# breakout.net
KiCad netlist of a schematic drawn in EAGLE
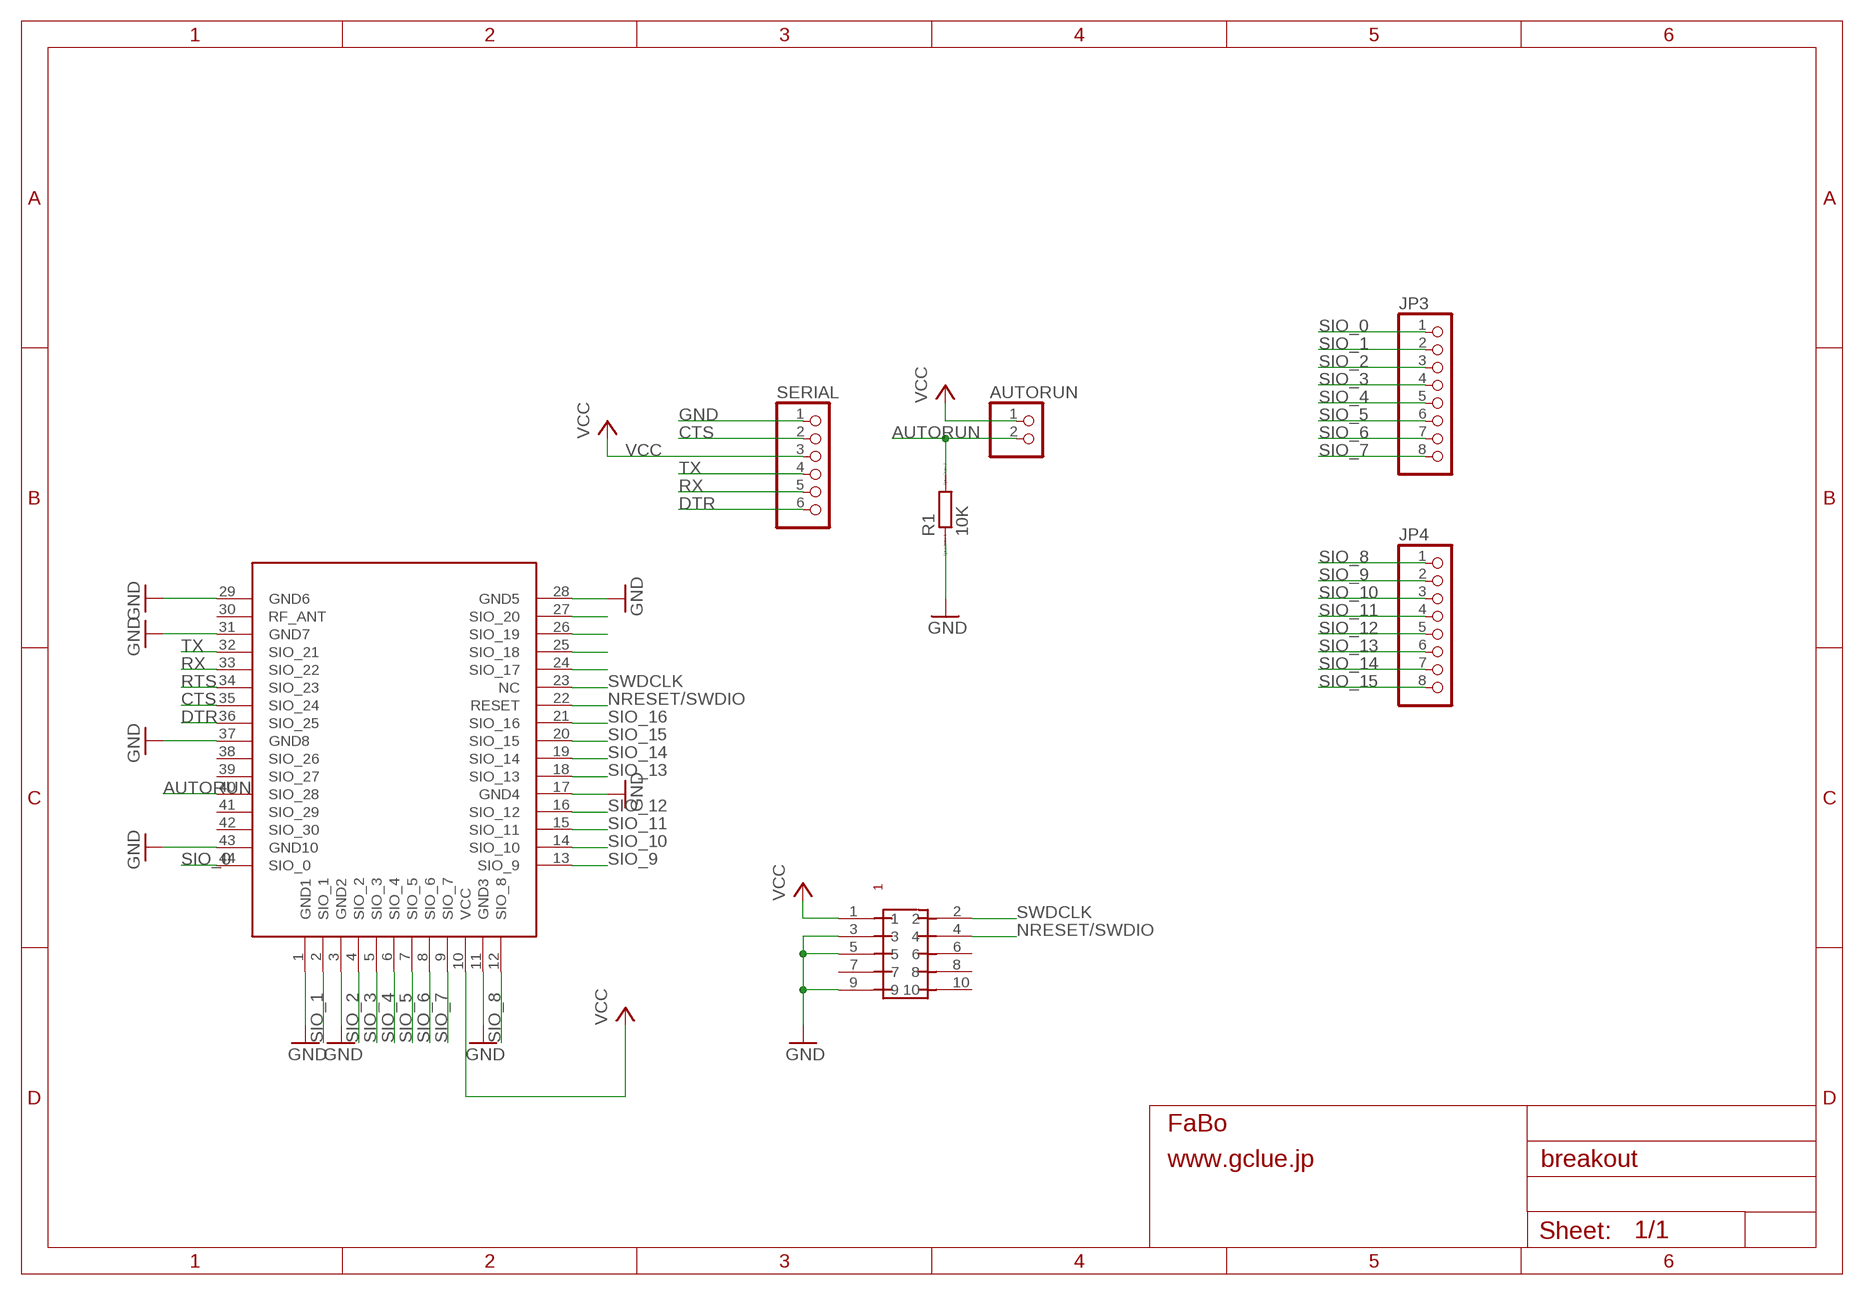
[diagram p0: schematic, sheet 1]

(export (version "E")
  (design (tool "Eeschema 10.0.6"))
  (components
    (comp (ref "AUTORUN")
      (value "PINHD-1X2")
      (footprint "eagle-import:1X02")
      (libsource (lib "eagle-import") (part "PINHD-1X2"))
    )
    (comp (ref "BL1")
      (value "LAIRD-BL600")
      (footprint "eagle-import:LAIRD-BL600")
      (libsource (lib "eagle-import") (part "LAIRD-BL600"))
    )
    (comp (ref "JP3")
      (value "PINHD-1X8-3.5MM")
      (footprint "eagle-import:1X08-3.5MM")
      (libsource (lib "eagle-import") (part "PINHD-1X8-3.5MM"))
    )
    (comp (ref "JP4")
      (value "PINHD-1X8-3.5MM")
      (footprint "eagle-import:1X08-3.5MM")
      (libsource (lib "eagle-import") (part "PINHD-1X8-3.5MM"))
    )
    (comp (ref "R1")
      (value "10K")
      (footprint "eagle-import:R0603")
      (libsource (lib "eagle-import") (part "RR0603"))
    )
    (comp (ref "SERIAL")
      (value "PINHD-1X6")
      (footprint "eagle-import:1X06")
      (libsource (lib "eagle-import") (part "PINHD-1X6"))
    )
    (comp (ref "U$1")
      (value "PIN-HEADER-SMT(1.27MM)2X5")
      (footprint "eagle-import:PIN-HEADER-SMT(1.27MM)2X5")
      (libsource (lib "eagle-import") (part "PIN-HEADER-SMT(1.27MM)2X5"))
    )
  )
  (nets
    (net (code "1") (name "/AUTORUN") (class "Default")
      (node (ref "AUTORUN") (pin "2") (pinfunction "2_2") (pintype "passive"))
      (node (ref "BL1") (pin "40") (pinfunction "SIO_28_40") (pintype "bidirectional"))
      (node (ref "R1") (pin "2") (pinfunction "2_2") (pintype "passive"))
    )
    (net (code "2") (name "/CTS") (class "Default")
      (node (ref "BL1") (pin "35") (pinfunction "SIO_24_35") (pintype "bidirectional"))
      (node (ref "SERIAL") (pin "2") (pinfunction "2_2") (pintype "passive"))
    )
    (net (code "3") (name "/DTR") (class "Default")
      (node (ref "BL1") (pin "36") (pinfunction "SIO_25_36") (pintype "bidirectional"))
      (node (ref "SERIAL") (pin "6") (pinfunction "6_6") (pintype "passive"))
    )
    (net (code "4") (name "/NRESET{slash}SWDIO") (class "Default")
      (node (ref "BL1") (pin "22") (pinfunction "RESET_22") (pintype "bidirectional"))
      (node (ref "U$1") (pin "4") (pinfunction "4_4") (pintype "bidirectional"))
    )
    (net (code "5") (name "/RTS") (class "Default")
      (node (ref "BL1") (pin "34") (pinfunction "SIO_23_34") (pintype "bidirectional"))
    )
    (net (code "6") (name "/RX") (class "Default")
      (node (ref "BL1") (pin "33") (pinfunction "SIO_22_33") (pintype "bidirectional"))
      (node (ref "SERIAL") (pin "5") (pinfunction "5_5") (pintype "passive"))
    )
    (net (code "7") (name "/SIO_0") (class "Default")
      (node (ref "BL1") (pin "44") (pinfunction "SIO_0_44") (pintype "bidirectional"))
      (node (ref "JP3") (pin "1") (pinfunction "1_1") (pintype "passive"))
    )
    (net (code "8") (name "/SIO_1") (class "Default")
      (node (ref "BL1") (pin "2") (pinfunction "SIO_1_2") (pintype "bidirectional"))
      (node (ref "JP3") (pin "2") (pinfunction "2_2") (pintype "passive"))
    )
    (net (code "9") (name "/SIO_2") (class "Default")
      (node (ref "BL1") (pin "4") (pinfunction "SIO_2_4") (pintype "bidirectional"))
      (node (ref "JP3") (pin "3") (pinfunction "3_3") (pintype "passive"))
    )
    (net (code "10") (name "/SIO_3") (class "Default")
      (node (ref "BL1") (pin "5") (pinfunction "SIO_3_5") (pintype "bidirectional"))
      (node (ref "JP3") (pin "4") (pinfunction "4_4") (pintype "passive"))
    )
    (net (code "11") (name "/SIO_4") (class "Default")
      (node (ref "BL1") (pin "6") (pinfunction "SIO_4_6") (pintype "bidirectional"))
      (node (ref "JP3") (pin "5") (pinfunction "5_5") (pintype "passive"))
    )
    (net (code "12") (name "/SIO_5") (class "Default")
      (node (ref "BL1") (pin "7") (pinfunction "SIO_5_7") (pintype "bidirectional"))
      (node (ref "JP3") (pin "6") (pinfunction "6_6") (pintype "passive"))
    )
    (net (code "13") (name "/SIO_6") (class "Default")
      (node (ref "BL1") (pin "8") (pinfunction "SIO_6_8") (pintype "bidirectional"))
      (node (ref "JP3") (pin "7") (pinfunction "7_7") (pintype "passive"))
    )
    (net (code "14") (name "/SIO_7") (class "Default")
      (node (ref "BL1") (pin "9") (pinfunction "SIO_7_9") (pintype "bidirectional"))
      (node (ref "JP3") (pin "8") (pinfunction "8_8") (pintype "passive"))
    )
    (net (code "15") (name "/SIO_8") (class "Default")
      (node (ref "BL1") (pin "12") (pinfunction "SIO_8_12") (pintype "bidirectional"))
      (node (ref "JP4") (pin "1") (pinfunction "1_1") (pintype "passive"))
    )
    (net (code "16") (name "/SIO_9") (class "Default")
      (node (ref "BL1") (pin "13") (pinfunction "SIO_9_13") (pintype "bidirectional"))
      (node (ref "JP4") (pin "2") (pinfunction "2_2") (pintype "passive"))
    )
    (net (code "17") (name "/SIO_10") (class "Default")
      (node (ref "BL1") (pin "14") (pinfunction "SIO_10_14") (pintype "bidirectional"))
      (node (ref "JP4") (pin "3") (pinfunction "3_3") (pintype "passive"))
    )
    (net (code "18") (name "/SIO_11") (class "Default")
      (node (ref "BL1") (pin "15") (pinfunction "SIO_11_15") (pintype "bidirectional"))
      (node (ref "JP4") (pin "4") (pinfunction "4_4") (pintype "passive"))
    )
    (net (code "19") (name "/SIO_12") (class "Default")
      (node (ref "BL1") (pin "16") (pinfunction "SIO_12_16") (pintype "bidirectional"))
      (node (ref "JP4") (pin "5") (pinfunction "5_5") (pintype "passive"))
    )
    (net (code "20") (name "/SIO_13") (class "Default")
      (node (ref "BL1") (pin "18") (pinfunction "SIO_13_18") (pintype "bidirectional"))
      (node (ref "JP4") (pin "6") (pinfunction "6_6") (pintype "passive"))
    )
    (net (code "21") (name "/SIO_14") (class "Default")
      (node (ref "BL1") (pin "19") (pinfunction "SIO_14_19") (pintype "bidirectional"))
      (node (ref "JP4") (pin "7") (pinfunction "7_7") (pintype "passive"))
    )
    (net (code "22") (name "/SIO_15") (class "Default")
      (node (ref "BL1") (pin "20") (pinfunction "SIO_15_20") (pintype "bidirectional"))
      (node (ref "JP4") (pin "8") (pinfunction "8_8") (pintype "passive"))
    )
    (net (code "23") (name "/SIO_16") (class "Default")
      (node (ref "BL1") (pin "21") (pinfunction "SIO_16_21") (pintype "bidirectional"))
    )
    (net (code "24") (name "/SWDCLK") (class "Default")
      (node (ref "BL1") (pin "23") (pinfunction "NC_23") (pintype "bidirectional"))
      (node (ref "U$1") (pin "2") (pinfunction "2_2") (pintype "bidirectional"))
    )
    (net (code "25") (name "/TX") (class "Default")
      (node (ref "BL1") (pin "32") (pinfunction "SIO_21_32") (pintype "bidirectional"))
      (node (ref "SERIAL") (pin "4") (pinfunction "4_4") (pintype "passive"))
    )
    (net (code "26") (name "GND") (class "Default")
      (node (ref "BL1") (pin "1") (pinfunction "GND1_1") (pintype "bidirectional"))
      (node (ref "BL1") (pin "11") (pinfunction "GND3_11") (pintype "bidirectional"))
      (node (ref "BL1") (pin "17") (pinfunction "GND4_17") (pintype "bidirectional"))
      (node (ref "BL1") (pin "28") (pinfunction "GND5_28") (pintype "bidirectional"))
      (node (ref "BL1") (pin "29") (pinfunction "GND6_29") (pintype "bidirectional"))
      (node (ref "BL1") (pin "3") (pinfunction "GND2_3") (pintype "bidirectional"))
      (node (ref "BL1") (pin "31") (pinfunction "GND7_31") (pintype "bidirectional"))
      (node (ref "BL1") (pin "37") (pinfunction "GND8_37") (pintype "bidirectional"))
      (node (ref "BL1") (pin "43") (pinfunction "GND10_43") (pintype "bidirectional"))
      (node (ref "R1") (pin "1") (pinfunction "1_1") (pintype "passive"))
      (node (ref "SERIAL") (pin "1") (pinfunction "1_1") (pintype "passive"))
      (node (ref "U$1") (pin "3") (pinfunction "3_3") (pintype "bidirectional"))
      (node (ref "U$1") (pin "5") (pinfunction "5_5") (pintype "bidirectional"))
      (node (ref "U$1") (pin "9") (pinfunction "9_9") (pintype "bidirectional"))
    )
    (net (code "27") (name "VCC") (class "Default")
      (node (ref "AUTORUN") (pin "1") (pinfunction "1_1") (pintype "passive"))
      (node (ref "BL1") (pin "10") (pinfunction "VCC_10") (pintype "bidirectional"))
      (node (ref "SERIAL") (pin "3") (pinfunction "3_3") (pintype "passive"))
      (node (ref "U$1") (pin "1") (pinfunction "1_1") (pintype "bidirectional"))
    )
    (net (code "28") (name "unconnected-(BL1-RF_ANT-Pad30)") (class "Default")
      (node (ref "BL1") (pin "30") (pinfunction "RF_ANT_30") (pintype "bidirectional"))
    )
    (net (code "29") (name "unconnected-(BL1-SIO_17-Pad24)") (class "Default")
      (node (ref "BL1") (pin "24") (pinfunction "SIO_17_24") (pintype "bidirectional"))
    )
    (net (code "30") (name "unconnected-(BL1-SIO_18-Pad25)") (class "Default")
      (node (ref "BL1") (pin "25") (pinfunction "SIO_18_25") (pintype "bidirectional"))
    )
    (net (code "31") (name "unconnected-(BL1-SIO_19-Pad26)") (class "Default")
      (node (ref "BL1") (pin "26") (pinfunction "SIO_19_26") (pintype "bidirectional"))
    )
    (net (code "32") (name "unconnected-(BL1-SIO_20-Pad27)") (class "Default")
      (node (ref "BL1") (pin "27") (pinfunction "SIO_20_27") (pintype "bidirectional"))
    )
    (net (code "33") (name "unconnected-(BL1-SIO_26-Pad38)") (class "Default")
      (node (ref "BL1") (pin "38") (pinfunction "SIO_26_38") (pintype "bidirectional"))
    )
    (net (code "34") (name "unconnected-(BL1-SIO_27-Pad39)") (class "Default")
      (node (ref "BL1") (pin "39") (pinfunction "SIO_27_39") (pintype "bidirectional"))
    )
    (net (code "35") (name "unconnected-(BL1-SIO_29-Pad41)") (class "Default")
      (node (ref "BL1") (pin "41") (pinfunction "SIO_29_41") (pintype "bidirectional"))
    )
    (net (code "36") (name "unconnected-(BL1-SIO_30-Pad42)") (class "Default")
      (node (ref "BL1") (pin "42") (pinfunction "SIO_30_42") (pintype "bidirectional"))
    )
    (net (code "37") (name "unconnected-(U$1-Pad6)") (class "Default")
      (node (ref "U$1") (pin "6") (pinfunction "6_6") (pintype "bidirectional"))
    )
    (net (code "38") (name "unconnected-(U$1-Pad7)") (class "Default")
      (node (ref "U$1") (pin "7") (pinfunction "7_7") (pintype "bidirectional"))
    )
    (net (code "39") (name "unconnected-(U$1-Pad8)") (class "Default")
      (node (ref "U$1") (pin "8") (pinfunction "8_8") (pintype "bidirectional"))
    )
    (net (code "40") (name "unconnected-(U$1-Pad10)") (class "Default")
      (node (ref "U$1") (pin "10") (pinfunction "10_10") (pintype "bidirectional"))
    )
  )
)
